# Section_C_EXP.net
KiCad netlist of a schematic drawn in Altium Designer
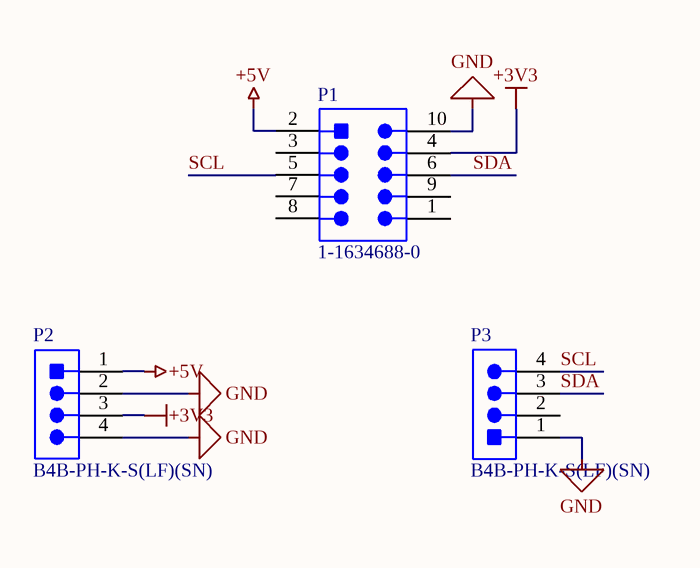
[diagram p0: Section_C_EXP.SchDoc]

(export (version "E")
  (design (tool "Eeschema 10.0.6"))
  (components
    (comp (ref "P1")
      (value "1-1634688-0")
      (footprint "TECO-1-1634688-0-10_V")
      (fields (field (name "MANUFACTURER") "TE Connectivity"))
      (libsource (lib "Altium Content Vault") (part "CN-2P-M-R10"))
    )
    (comp (ref "P2")
      (value "B4B-PH-K-S(LF)(SN)")
      (footprint "JST-B4B-PH-K-S_V")
      (fields (field (name "MANUFACTURER") "JST"))
      (libsource (lib "Altium Content Vault") (part "CN-1P-M-R4"))
    )
    (comp (ref "P3")
      (value "B4B-PH-K-S(LF)(SN)")
      (footprint "JST-B4B-PH-K-S_V")
      (fields (field (name "MANUFACTURER") "JST"))
      (libsource (lib "") (part "CN-1P-M-R4_1"))
    )
  )
  (nets
    (net (code "1") (name "+3V3") (class "Default")
      (node (ref "P1") (pin "4") (pinfunction "4_4") (pintype "passive"))
      (node (ref "P2") (pin "3") (pinfunction "3_3") (pintype "passive"))
    )
    (net (code "2") (name "+5V") (class "Default")
      (node (ref "P1") (pin "2") (pinfunction "2_2") (pintype "passive"))
      (node (ref "P2") (pin "1") (pinfunction "1_1") (pintype "passive"))
    )
    (net (code "3") (name "/SCL") (class "Default")
      (node (ref "P1") (pin "5") (pinfunction "5_5") (pintype "passive"))
      (node (ref "P3") (pin "4") (pinfunction "4_4") (pintype "passive"))
    )
    (net (code "4") (name "/SDA") (class "Default")
      (node (ref "P1") (pin "6") (pinfunction "6_6") (pintype "passive"))
      (node (ref "P3") (pin "3") (pinfunction "3_3") (pintype "passive"))
    )
    (net (code "5") (name "GND") (class "Default")
      (node (ref "P1") (pin "10") (pinfunction "10_10") (pintype "passive"))
      (node (ref "P2") (pin "2") (pinfunction "2_2") (pintype "passive"))
      (node (ref "P2") (pin "4") (pinfunction "4_4") (pintype "passive"))
      (node (ref "P3") (pin "1") (pinfunction "1_1") (pintype "passive"))
    )
    (net (code "6") (name "unconnected-(P1-Pad1)") (class "Default")
      (node (ref "P1") (pin "1") (pinfunction "1_1") (pintype "passive"))
    )
    (net (code "7") (name "unconnected-(P1-Pad3)") (class "Default")
      (node (ref "P1") (pin "3") (pinfunction "3_3") (pintype "passive"))
    )
    (net (code "8") (name "unconnected-(P1-Pad7)") (class "Default")
      (node (ref "P1") (pin "7") (pinfunction "7_7") (pintype "passive"))
    )
    (net (code "9") (name "unconnected-(P1-Pad8)") (class "Default")
      (node (ref "P1") (pin "8") (pinfunction "8_8") (pintype "passive"))
    )
    (net (code "10") (name "unconnected-(P1-Pad9)") (class "Default")
      (node (ref "P1") (pin "9") (pinfunction "9_9") (pintype "passive"))
    )
    (net (code "11") (name "unconnected-(P3-Pad2)") (class "Default")
      (node (ref "P3") (pin "2") (pinfunction "2_2") (pintype "passive"))
    )
  )
)
